# Exposure_Timer_Button_Panel.net
KiCad netlist of a schematic drawn in EAGLE
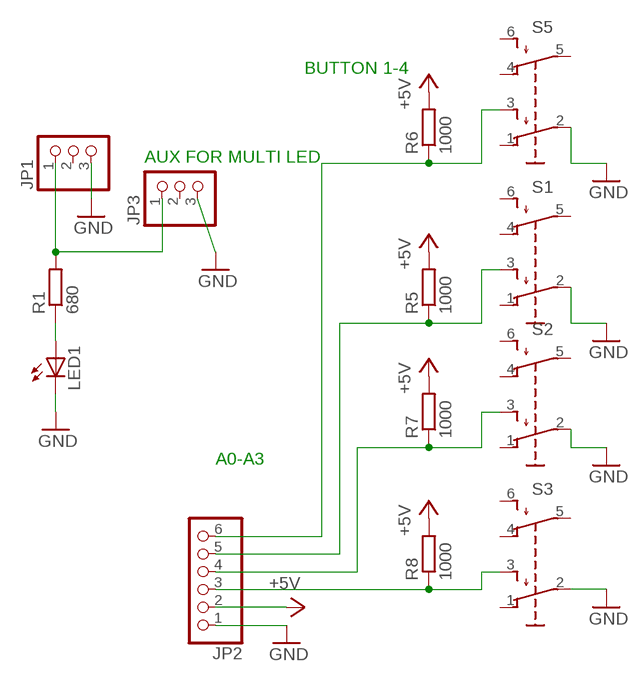
[diagram p0: schematic, sheet 1]

(export (version "E")
  (design (tool "Eeschema 10.0.6"))
  (components
    (comp (ref "JP1")
      (value "PINHD-1X3")
      (footprint "eagle-import:1X03")
      (libsource (lib "eagle-import") (part "PINHD-1X3"))
    )
    (comp (ref "JP2")
      (value "PINHD-1X6")
      (footprint "eagle-import:1X06")
      (libsource (lib "eagle-import") (part "PINHD-1X6"))
    )
    (comp (ref "JP3")
      (value "PINHD-1X3")
      (footprint "eagle-import:1X03")
      (libsource (lib "eagle-import") (part "PINHD-1X3"))
    )
    (comp (ref "LED1")
      (value "LED5MM")
      (footprint "eagle-import:LED5MM")
      (libsource (lib "eagle-import") (part "LED5MM"))
    )
    (comp (ref "R1")
      (value "680")
      (footprint "eagle-import:0204_7")
      (libsource (lib "eagle-import") (part "R-EU_0204/7"))
    )
    (comp (ref "R5")
      (value "1000")
      (footprint "eagle-import:0204_7")
      (libsource (lib "eagle-import") (part "R-EU_0204/7"))
    )
    (comp (ref "R6")
      (value "1000")
      (footprint "eagle-import:0204_7")
      (libsource (lib "eagle-import") (part "R-EU_0204/7"))
    )
    (comp (ref "R7")
      (value "1000")
      (footprint "eagle-import:0204_7")
      (libsource (lib "eagle-import") (part "R-EU_0204/7"))
    )
    (comp (ref "R8")
      (value "1000")
      (footprint "eagle-import:0204_7")
      (libsource (lib "eagle-import") (part "R-EU_0204/7"))
    )
    (comp (ref "S1")
      (value "TL42PO")
      (footprint "eagle-import:TL4XPO")
      (libsource (lib "eagle-import") (part "TL42PO"))
    )
    (comp (ref "S2")
      (value "TL42PO")
      (footprint "eagle-import:TL4XPO")
      (libsource (lib "eagle-import") (part "TL42PO"))
    )
    (comp (ref "S3")
      (value "TL42PO")
      (footprint "eagle-import:TL4XPO")
      (libsource (lib "eagle-import") (part "TL42PO"))
    )
    (comp (ref "S5")
      (value "TL42PO")
      (footprint "eagle-import:TL4XPO")
      (libsource (lib "eagle-import") (part "TL42PO"))
    )
  )
  (nets
    (net (code "1") (name "+5V") (class "Default")
      (node (ref "JP2") (pin "2") (pinfunction "2_2") (pintype "passive"))
      (node (ref "R5") (pin "2") (pinfunction "2_2") (pintype "passive"))
      (node (ref "R6") (pin "2") (pinfunction "2_2") (pintype "passive"))
      (node (ref "R7") (pin "2") (pinfunction "2_2") (pintype "passive"))
      (node (ref "R8") (pin "2") (pinfunction "2_2") (pintype "passive"))
    )
    (net (code "2") (name "GND") (class "Default")
      (node (ref "JP1") (pin "3") (pinfunction "3_3") (pintype "passive"))
      (node (ref "JP2") (pin "1") (pinfunction "1_1") (pintype "passive"))
      (node (ref "JP3") (pin "3") (pinfunction "3_3") (pintype "passive"))
      (node (ref "LED1") (pin "K") (pinfunction "C_K") (pintype "passive"))
      (node (ref "S1") (pin "2") (pinfunction "P_2") (pintype "passive"))
      (node (ref "S2") (pin "2") (pinfunction "P_2") (pintype "passive"))
      (node (ref "S3") (pin "2") (pinfunction "P_2") (pintype "passive"))
      (node (ref "S5") (pin "2") (pinfunction "P_2") (pintype "passive"))
    )
    (net (code "3") (name "Net-(JP1-Pad1)") (class "Default")
      (node (ref "JP1") (pin "1") (pinfunction "1_1") (pintype "passive"))
      (node (ref "JP3") (pin "1") (pinfunction "1_1") (pintype "passive"))
      (node (ref "R1") (pin "2") (pinfunction "2_2") (pintype "passive"))
    )
    (net (code "4") (name "Net-(LED1-PadA)") (class "Default")
      (node (ref "LED1") (pin "A") (pinfunction "A_A") (pintype "passive"))
      (node (ref "R1") (pin "1") (pinfunction "1_1") (pintype "passive"))
    )
    (net (code "5") (name "Net-(S1-S)") (class "Default")
      (node (ref "JP2") (pin "5") (pinfunction "5_5") (pintype "passive"))
      (node (ref "R5") (pin "1") (pinfunction "1_1") (pintype "passive"))
      (node (ref "S1") (pin "3") (pinfunction "S_3") (pintype "passive"))
    )
    (net (code "6") (name "Net-(S2-S)") (class "Default")
      (node (ref "JP2") (pin "4") (pinfunction "4_4") (pintype "passive"))
      (node (ref "R7") (pin "1") (pinfunction "1_1") (pintype "passive"))
      (node (ref "S2") (pin "3") (pinfunction "S_3") (pintype "passive"))
    )
    (net (code "7") (name "Net-(S3-S)") (class "Default")
      (node (ref "JP2") (pin "3") (pinfunction "3_3") (pintype "passive"))
      (node (ref "R8") (pin "1") (pinfunction "1_1") (pintype "passive"))
      (node (ref "S3") (pin "3") (pinfunction "S_3") (pintype "passive"))
    )
    (net (code "8") (name "Net-(S5-S)") (class "Default")
      (node (ref "JP2") (pin "6") (pinfunction "6_6") (pintype "passive"))
      (node (ref "R6") (pin "1") (pinfunction "1_1") (pintype "passive"))
      (node (ref "S5") (pin "3") (pinfunction "S_3") (pintype "passive"))
    )
    (net (code "9") (name "unconnected-(JP1-Pad2)") (class "Default")
      (node (ref "JP1") (pin "2") (pinfunction "2_2") (pintype "passive"))
    )
    (net (code "10") (name "unconnected-(JP3-Pad2)") (class "Default")
      (node (ref "JP3") (pin "2") (pinfunction "2_2") (pintype "passive"))
    )
    (net (code "11") (name "unconnected-(S1-O-Pad1)") (class "Default")
      (node (ref "S1") (pin "1") (pinfunction "O_1") (pintype "passive"))
    )
    (net (code "12") (name "unconnected-(S1-O1-Pad4)") (class "Default")
      (node (ref "S1") (pin "4") (pinfunction "O1_4") (pintype "passive"))
    )
    (net (code "13") (name "unconnected-(S1-P1-Pad5)") (class "Default")
      (node (ref "S1") (pin "5") (pinfunction "P1_5") (pintype "passive"))
    )
    (net (code "14") (name "unconnected-(S1-S1-Pad6)") (class "Default")
      (node (ref "S1") (pin "6") (pinfunction "S1_6") (pintype "passive"))
    )
    (net (code "15") (name "unconnected-(S2-O-Pad1)") (class "Default")
      (node (ref "S2") (pin "1") (pinfunction "O_1") (pintype "passive"))
    )
    (net (code "16") (name "unconnected-(S2-O1-Pad4)") (class "Default")
      (node (ref "S2") (pin "4") (pinfunction "O1_4") (pintype "passive"))
    )
    (net (code "17") (name "unconnected-(S2-P1-Pad5)") (class "Default")
      (node (ref "S2") (pin "5") (pinfunction "P1_5") (pintype "passive"))
    )
    (net (code "18") (name "unconnected-(S2-S1-Pad6)") (class "Default")
      (node (ref "S2") (pin "6") (pinfunction "S1_6") (pintype "passive"))
    )
    (net (code "19") (name "unconnected-(S3-O-Pad1)") (class "Default")
      (node (ref "S3") (pin "1") (pinfunction "O_1") (pintype "passive"))
    )
    (net (code "20") (name "unconnected-(S3-O1-Pad4)") (class "Default")
      (node (ref "S3") (pin "4") (pinfunction "O1_4") (pintype "passive"))
    )
    (net (code "21") (name "unconnected-(S3-P1-Pad5)") (class "Default")
      (node (ref "S3") (pin "5") (pinfunction "P1_5") (pintype "passive"))
    )
    (net (code "22") (name "unconnected-(S3-S1-Pad6)") (class "Default")
      (node (ref "S3") (pin "6") (pinfunction "S1_6") (pintype "passive"))
    )
    (net (code "23") (name "unconnected-(S5-O-Pad1)") (class "Default")
      (node (ref "S5") (pin "1") (pinfunction "O_1") (pintype "passive"))
    )
    (net (code "24") (name "unconnected-(S5-O1-Pad4)") (class "Default")
      (node (ref "S5") (pin "4") (pinfunction "O1_4") (pintype "passive"))
    )
    (net (code "25") (name "unconnected-(S5-P1-Pad5)") (class "Default")
      (node (ref "S5") (pin "5") (pinfunction "P1_5") (pintype "passive"))
    )
    (net (code "26") (name "unconnected-(S5-S1-Pad6)") (class "Default")
      (node (ref "S5") (pin "6") (pinfunction "S1_6") (pintype "passive"))
    )
  )
)
